# snc98_3x4_Switch-futuba.net
KiCad netlist of a schematic drawn in EAGLE
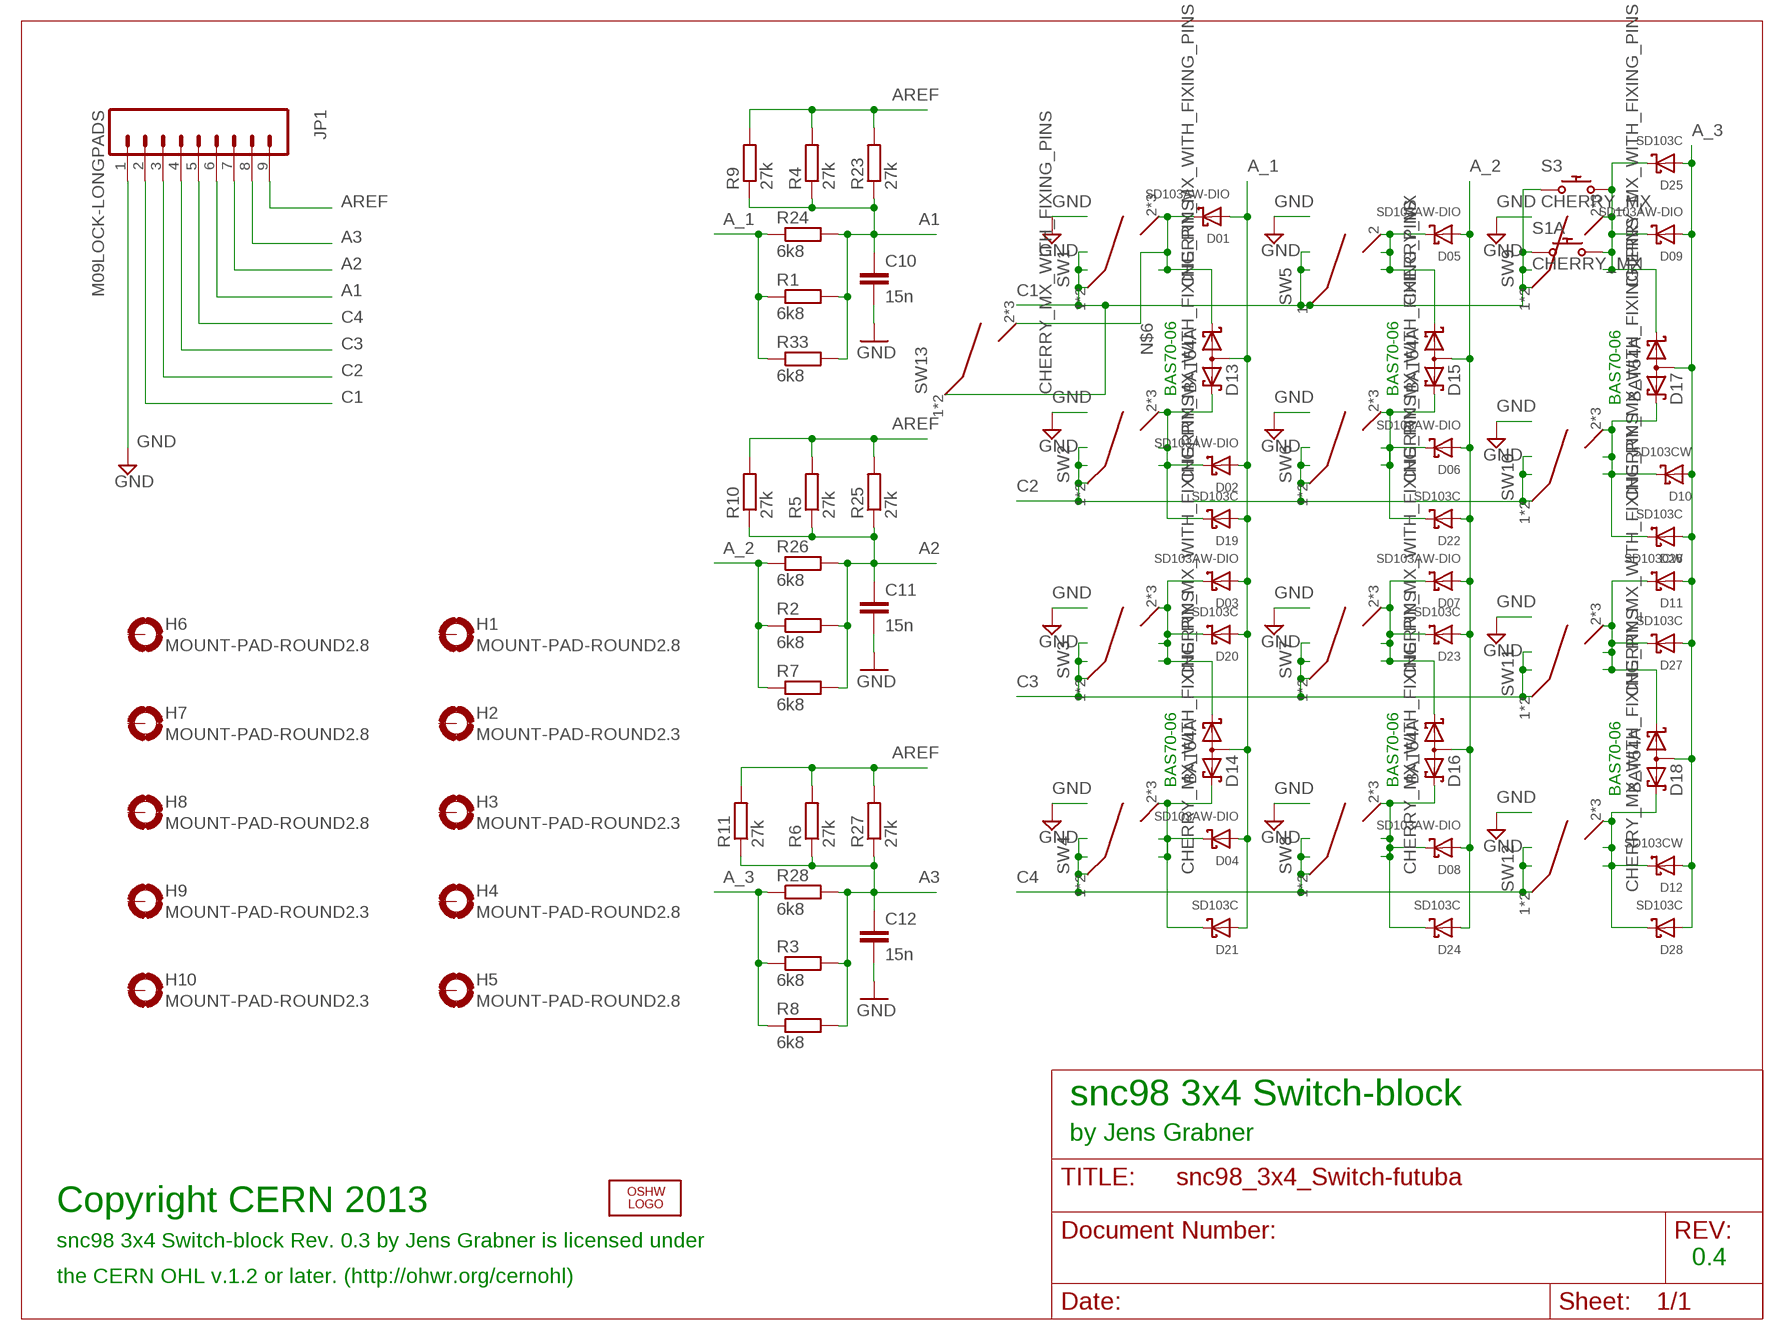
[diagram p0: schematic, sheet 1]

(export (version "E")
  (design (tool "Eeschema 10.0.6"))
  (components
    (comp (ref "C10")
      (value "15n")
      (footprint "eagle-import:C1206K")
      (libsource (lib "eagle-import") (part "C-EUC1206K"))
    )
    (comp (ref "C11")
      (value "15n")
      (footprint "eagle-import:C1206K")
      (libsource (lib "eagle-import") (part "C-EUC1206K"))
    )
    (comp (ref "C12")
      (value "15n")
      (footprint "eagle-import:C1206K")
      (libsource (lib "eagle-import") (part "C-EUC1206K"))
    )
    (comp (ref "D01")
      (value "SD103AW-DIO")
      (footprint "eagle-import:SOD-123F")
      (fields (field (name "MF") "MULTICOMP") (field (name "MPN") "SD103CW-7-F"))
      (libsource (lib "eagle-import") (part "DIODESOD-123F"))
    )
    (comp (ref "D02")
      (value "SD103AW-DIO")
      (footprint "eagle-import:SOD-123F")
      (fields (field (name "MF") "MULTICOMP") (field (name "MPN") "SD103CW-7-F"))
      (libsource (lib "eagle-import") (part "DIODESOD-123F"))
    )
    (comp (ref "D03")
      (value "SD103AW-DIO")
      (footprint "eagle-import:SOD-123F")
      (fields (field (name "MF") "MULTICOMP") (field (name "MPN") "SD103CW-7-F"))
      (libsource (lib "eagle-import") (part "DIODESOD-123F"))
    )
    (comp (ref "D04")
      (value "SD103AW-DIO")
      (footprint "eagle-import:SOD-123F")
      (fields (field (name "MF") "MULTICOMP") (field (name "MPN") "SD103CW-7-F"))
      (libsource (lib "eagle-import") (part "DIODESOD-123F"))
    )
    (comp (ref "D05")
      (value "SD103AW-DIO")
      (footprint "eagle-import:SOD-123F")
      (fields (field (name "MF") "MULTICOMP") (field (name "MPN") "SD103CW-7-F"))
      (libsource (lib "eagle-import") (part "DIODESOD-123F"))
    )
    (comp (ref "D06")
      (value "SD103AW-DIO")
      (footprint "eagle-import:SOD-123F")
      (fields (field (name "MF") "MULTICOMP") (field (name "MPN") "SD103CW-7-F"))
      (libsource (lib "eagle-import") (part "DIODESOD-123F"))
    )
    (comp (ref "D07")
      (value "SD103AW-DIO")
      (footprint "eagle-import:SOD-123F")
      (fields (field (name "MF") "MULTICOMP") (field (name "MPN") "SD103CW-7-F"))
      (libsource (lib "eagle-import") (part "DIODESOD-123F"))
    )
    (comp (ref "D08")
      (value "SD103AW-DIO")
      (footprint "eagle-import:SOD-123F")
      (fields (field (name "MF") "MULTICOMP") (field (name "MPN") "SD103CW-7-F"))
      (libsource (lib "eagle-import") (part "DIODESOD-123F"))
    )
    (comp (ref "D09")
      (value "SD103AW-DIO")
      (footprint "eagle-import:SOD-123F")
      (fields (field (name "MF") "MULTICOMP") (field (name "MPN") "SD103CW-7-F"))
      (libsource (lib "eagle-import") (part "DIODESOD-123F"))
    )
    (comp (ref "D10")
      (value "SD103CW")
      (footprint "eagle-import:SOD-123F")
      (fields (field (name "MF") "MULTICOMP") (field (name "MPN") "SD103CW-7-F"))
      (libsource (lib "eagle-import") (part "DIODESOD-123F"))
    )
    (comp (ref "D11")
      (value "SD103CW")
      (footprint "eagle-import:SOD-123F")
      (fields (field (name "MF") "MULTICOMP") (field (name "MPN") "SD103CW-7-F"))
      (libsource (lib "eagle-import") (part "DIODESOD-123F"))
    )
    (comp (ref "D12")
      (value "SD103CW")
      (footprint "eagle-import:SOD-123F")
      (fields (field (name "MF") "MULTICOMP") (field (name "MPN") "SD103CW-7-F"))
      (libsource (lib "eagle-import") (part "DIODESOD-123F"))
    )
    (comp (ref "D13")
      (value "BAT54A")
      (footprint "eagle-import:SOT23")
      (libsource (lib "eagle-import") (part "BAT54A"))
    )
    (comp (ref "D14")
      (value "BAT54A")
      (footprint "eagle-import:SOT23")
      (libsource (lib "eagle-import") (part "BAT54A"))
    )
    (comp (ref "D15")
      (value "BAT54A")
      (footprint "eagle-import:SOT23")
      (libsource (lib "eagle-import") (part "BAT54A"))
    )
    (comp (ref "D16")
      (value "BAT54A")
      (footprint "eagle-import:SOT23")
      (libsource (lib "eagle-import") (part "BAT54A"))
    )
    (comp (ref "D17")
      (value "BAT54A")
      (footprint "eagle-import:SOT23")
      (libsource (lib "eagle-import") (part "BAT54A"))
    )
    (comp (ref "D18")
      (value "BAT54A")
      (footprint "eagle-import:SOT23")
      (libsource (lib "eagle-import") (part "BAT54A"))
    )
    (comp (ref "D19")
      (value "SD103C")
      (footprint "eagle-import:280MIL-TH")
      (fields (field (name "MF") "MULTICOMP") (field (name "MPN") "SD103CW-7-F"))
      (libsource (lib "eagle-import") (part "DIODE280MIL-TH"))
    )
    (comp (ref "D20")
      (value "SD103C")
      (footprint "eagle-import:280MIL-TH")
      (fields (field (name "MF") "MULTICOMP") (field (name "MPN") "SD103CW-7-F"))
      (libsource (lib "eagle-import") (part "DIODE280MIL-TH"))
    )
    (comp (ref "D21")
      (value "SD103C")
      (footprint "eagle-import:280MIL-TH")
      (fields (field (name "MF") "MULTICOMP") (field (name "MPN") "SD103CW-7-F"))
      (libsource (lib "eagle-import") (part "DIODE280MIL-TH"))
    )
    (comp (ref "D22")
      (value "SD103C")
      (footprint "eagle-import:280MIL-TH")
      (fields (field (name "MF") "MULTICOMP") (field (name "MPN") "SD103CW-7-F"))
      (libsource (lib "eagle-import") (part "DIODE280MIL-TH"))
    )
    (comp (ref "D23")
      (value "SD103C")
      (footprint "eagle-import:280MIL-TH")
      (fields (field (name "MF") "MULTICOMP") (field (name "MPN") "SD103CW-7-F"))
      (libsource (lib "eagle-import") (part "DIODE280MIL-TH"))
    )
    (comp (ref "D24")
      (value "SD103C")
      (footprint "eagle-import:280MIL-TH")
      (fields (field (name "MF") "MULTICOMP") (field (name "MPN") "SD103CW-7-F"))
      (libsource (lib "eagle-import") (part "DIODE280MIL-TH"))
    )
    (comp (ref "D25")
      (value "SD103C")
      (footprint "eagle-import:280MIL-TH")
      (fields (field (name "MF") "MULTICOMP") (field (name "MPN") "SD103CW-7-F"))
      (libsource (lib "eagle-import") (part "DIODE280MIL-TH"))
    )
    (comp (ref "D26")
      (value "SD103C")
      (footprint "eagle-import:280MIL-TH")
      (fields (field (name "MF") "MULTICOMP") (field (name "MPN") "SD103CW-7-F"))
      (libsource (lib "eagle-import") (part "DIODE280MIL-TH"))
    )
    (comp (ref "D27")
      (value "SD103C")
      (footprint "eagle-import:280MIL-TH")
      (fields (field (name "MF") "MULTICOMP") (field (name "MPN") "SD103CW-7-F"))
      (libsource (lib "eagle-import") (part "DIODE280MIL-TH"))
    )
    (comp (ref "D28")
      (value "SD103C")
      (footprint "eagle-import:280MIL-TH")
      (fields (field (name "MF") "MULTICOMP") (field (name "MPN") "SD103CW-7-F"))
      (libsource (lib "eagle-import") (part "DIODE280MIL-TH"))
    )
    (comp (ref "H1")
      (value "MOUNT-PAD-ROUND2.8")
      (footprint "eagle-import:2,8-PAD")
      (libsource (lib "eagle-import") (part "MOUNT-PAD-ROUND2.8"))
    )
    (comp (ref "H2")
      (value "MOUNT-PAD-ROUND2.3")
      (footprint "eagle-import:2,3-PAD")
      (libsource (lib "eagle-import") (part "MOUNT-PAD-ROUND2.3"))
    )
    (comp (ref "H3")
      (value "MOUNT-PAD-ROUND2.3")
      (footprint "eagle-import:2,3-PAD")
      (libsource (lib "eagle-import") (part "MOUNT-PAD-ROUND2.3"))
    )
    (comp (ref "H4")
      (value "MOUNT-PAD-ROUND2.8")
      (footprint "eagle-import:2,8-PAD")
      (libsource (lib "eagle-import") (part "MOUNT-PAD-ROUND2.8"))
    )
    (comp (ref "H5")
      (value "MOUNT-PAD-ROUND2.8")
      (footprint "eagle-import:2,8-PAD")
      (libsource (lib "eagle-import") (part "MOUNT-PAD-ROUND2.8"))
    )
    (comp (ref "H6")
      (value "MOUNT-PAD-ROUND2.8")
      (footprint "eagle-import:2,8-PAD")
      (libsource (lib "eagle-import") (part "MOUNT-PAD-ROUND2.8"))
    )
    (comp (ref "H7")
      (value "MOUNT-PAD-ROUND2.8")
      (footprint "eagle-import:2,8-PAD")
      (libsource (lib "eagle-import") (part "MOUNT-PAD-ROUND2.8"))
    )
    (comp (ref "H8")
      (value "MOUNT-PAD-ROUND2.8")
      (footprint "eagle-import:2,8-PAD")
      (libsource (lib "eagle-import") (part "MOUNT-PAD-ROUND2.8"))
    )
    (comp (ref "H9")
      (value "MOUNT-PAD-ROUND2.3")
      (footprint "eagle-import:2,3-PAD")
      (libsource (lib "eagle-import") (part "MOUNT-PAD-ROUND2.3"))
    )
    (comp (ref "H10")
      (value "MOUNT-PAD-ROUND2.3")
      (footprint "eagle-import:2,3-PAD")
      (libsource (lib "eagle-import") (part "MOUNT-PAD-ROUND2.3"))
    )
    (comp (ref "JP1")
      (value "M09LOCK-LONGPADS")
      (footprint "eagle-import:1X09_LOCK_LONGPADS")
      (libsource (lib "eagle-import") (part "M09LOCK-LONGPADS"))
    )
    (comp (ref "LOGO1")
      (value "OSHW_LOGO_8MILX0150-NT")
      (footprint "eagle-import:OSHW_8X150_NOTEXT")
      (libsource (lib "eagle-import") (part "OSHW_LOGO_8MILX0150-NT"))
    )
    (comp (ref "R1")
      (value "6k8")
      (footprint "eagle-import:R1206")
      (libsource (lib "eagle-import") (part "R-EU_R1206"))
    )
    (comp (ref "R2")
      (value "6k8")
      (footprint "eagle-import:R1206")
      (libsource (lib "eagle-import") (part "R-EU_R1206"))
    )
    (comp (ref "R3")
      (value "6k8")
      (footprint "eagle-import:R1206")
      (libsource (lib "eagle-import") (part "R-EU_R1206"))
    )
    (comp (ref "R4")
      (value "27k")
      (footprint "eagle-import:R1206")
      (libsource (lib "eagle-import") (part "R-EU_R1206"))
    )
    (comp (ref "R5")
      (value "27k")
      (footprint "eagle-import:R1206")
      (libsource (lib "eagle-import") (part "R-EU_R1206"))
    )
    (comp (ref "R6")
      (value "27k")
      (footprint "eagle-import:R1206")
      (libsource (lib "eagle-import") (part "R-EU_R1206"))
    )
    (comp (ref "R7")
      (value "6k8")
      (footprint "eagle-import:M0805")
      (libsource (lib "eagle-import") (part "R-EU_M0805"))
    )
    (comp (ref "R8")
      (value "6k8")
      (footprint "eagle-import:M0805")
      (libsource (lib "eagle-import") (part "R-EU_M0805"))
    )
    (comp (ref "R9")
      (value "27k")
      (footprint "eagle-import:M0805")
      (libsource (lib "eagle-import") (part "R-EU_M0805"))
    )
    (comp (ref "R10")
      (value "27k")
      (footprint "eagle-import:M0805")
      (libsource (lib "eagle-import") (part "R-EU_M0805"))
    )
    (comp (ref "R11")
      (value "27k")
      (footprint "eagle-import:M0805")
      (libsource (lib "eagle-import") (part "R-EU_M0805"))
    )
    (comp (ref "R23")
      (value "27k")
      (footprint "eagle-import:0204_5")
      (libsource (lib "eagle-import") (part "R-EU_0204/5"))
    )
    (comp (ref "R24")
      (value "6k8")
      (footprint "eagle-import:0204_5")
      (libsource (lib "eagle-import") (part "R-EU_0204/5"))
    )
    (comp (ref "R25")
      (value "27k")
      (footprint "eagle-import:0204_5")
      (libsource (lib "eagle-import") (part "R-EU_0204/5"))
    )
    (comp (ref "R26")
      (value "6k8")
      (footprint "eagle-import:0204_5")
      (libsource (lib "eagle-import") (part "R-EU_0204/5"))
    )
    (comp (ref "R27")
      (value "27k")
      (footprint "eagle-import:0204_5")
      (libsource (lib "eagle-import") (part "R-EU_0204/5"))
    )
    (comp (ref "R28")
      (value "6k8")
      (footprint "eagle-import:0204_5")
      (libsource (lib "eagle-import") (part "R-EU_0204/5"))
    )
    (comp (ref "R33")
      (value "6k8")
      (footprint "eagle-import:M0805")
      (libsource (lib "eagle-import") (part "R-EU_M0805"))
    )
    (comp (ref "S1A")
      (value "CHERRY_MX")
      (footprint "eagle-import:CHERRY_MX")
      (libsource (lib "eagle-import") (part "cherry_CHERRY_MX"))
    )
    (comp (ref "S3")
      (value "CHERRY_MX")
      (footprint "eagle-import:CHERRY_MX")
      (libsource (lib "eagle-import") (part "cherry_CHERRY_MX"))
    )
    (comp (ref "SW1")
      (value "CHERRY_MX_WITH_FIXING_PINS")
      (footprint "eagle-import:MX1A-XXNW")
      (libsource (lib "eagle-import") (part "CHERRY_MX_WITH_FIXING_PINS"))
    )
    (comp (ref "SW2")
      (value "CHERRY_MX_WITH_FIXING_PINS")
      (footprint "eagle-import:MX1A-XXNW")
      (libsource (lib "eagle-import") (part "CHERRY_MX_WITH_FIXING_PINS"))
    )
    (comp (ref "SW3")
      (value "CHERRY_MX_WITH_FIXING_PINS")
      (footprint "eagle-import:MX1A-XXNW")
      (libsource (lib "eagle-import") (part "CHERRY_MX_WITH_FIXING_PINS"))
    )
    (comp (ref "SW4")
      (value "CHERRY_MX_WITH_FIXING_PINS")
      (footprint "eagle-import:MX1A-XXNW")
      (libsource (lib "eagle-import") (part "CHERRY_MX_WITH_FIXING_PINS"))
    )
    (comp (ref "SW5")
      (value "CHERRY_MX")
      (footprint "eagle-import:MX1A-XXNN")
      (libsource (lib "eagle-import") (part "CHERRY_MX"))
    )
    (comp (ref "SW6")
      (value "CHERRY_MX_WITH_FIXING_PINS")
      (footprint "eagle-import:MX1A-XXNW")
      (libsource (lib "eagle-import") (part "CHERRY_MX_WITH_FIXING_PINS"))
    )
    (comp (ref "SW7")
      (value "CHERRY_MX_WITH_FIXING_PINS")
      (footprint "eagle-import:MX1A-XXNW")
      (libsource (lib "eagle-import") (part "CHERRY_MX_WITH_FIXING_PINS"))
    )
    (comp (ref "SW8")
      (value "CHERRY_MX_WITH_FIXING_PINS")
      (footprint "eagle-import:MX1A-XXNW")
      (libsource (lib "eagle-import") (part "CHERRY_MX_WITH_FIXING_PINS"))
    )
    (comp (ref "SW9")
      (value "CHERRY_MX_WITH_FIXING_PINS")
      (footprint "eagle-import:MX1A-XXNW")
      (libsource (lib "eagle-import") (part "CHERRY_MX_WITH_FIXING_PINS"))
    )
    (comp (ref "SW10")
      (value "CHERRY_MX_WITH_FIXING_PINS")
      (footprint "eagle-import:MX1A-XXNW")
      (libsource (lib "eagle-import") (part "CHERRY_MX_WITH_FIXING_PINS"))
    )
    (comp (ref "SW11")
      (value "CHERRY_MX_WITH_FIXING_PINS")
      (footprint "eagle-import:MX1A-XXNW")
      (libsource (lib "eagle-import") (part "CHERRY_MX_WITH_FIXING_PINS"))
    )
    (comp (ref "SW12")
      (value "CHERRY_MX_WITH_FIXING_PINS")
      (footprint "eagle-import:MX1A-XXNW")
      (libsource (lib "eagle-import") (part "CHERRY_MX_WITH_FIXING_PINS"))
    )
    (comp (ref "SW13")
      (value "CHERRY_MX_WITH_FIXING_PINS")
      (footprint "eagle-import:MX1A-XXNW")
      (libsource (lib "eagle-import") (part "CHERRY_MX_WITH_FIXING_PINS"))
    )
  )
  (nets
    (net (code "1") (name "/A1") (class "Default")
      (node (ref "C10") (pin "1") (pinfunction "1_1") (pintype "passive"))
      (node (ref "JP1") (pin "6") (pinfunction "6_6") (pintype "passive"))
      (node (ref "R1") (pin "2") (pinfunction "2_2") (pintype "passive"))
      (node (ref "R23") (pin "1") (pinfunction "1_1") (pintype "passive"))
      (node (ref "R24") (pin "2") (pinfunction "2_2") (pintype "passive"))
      (node (ref "R33") (pin "2") (pinfunction "2_2") (pintype "passive"))
      (node (ref "R4") (pin "1") (pinfunction "1_1") (pintype "passive"))
      (node (ref "R9") (pin "1") (pinfunction "1_1") (pintype "passive"))
    )
    (net (code "2") (name "/A2") (class "Default")
      (node (ref "C11") (pin "1") (pinfunction "1_1") (pintype "passive"))
      (node (ref "JP1") (pin "7") (pinfunction "7_7") (pintype "passive"))
      (node (ref "R10") (pin "1") (pinfunction "1_1") (pintype "passive"))
      (node (ref "R2") (pin "2") (pinfunction "2_2") (pintype "passive"))
      (node (ref "R25") (pin "1") (pinfunction "1_1") (pintype "passive"))
      (node (ref "R26") (pin "2") (pinfunction "2_2") (pintype "passive"))
      (node (ref "R5") (pin "1") (pinfunction "1_1") (pintype "passive"))
      (node (ref "R7") (pin "2") (pinfunction "2_2") (pintype "passive"))
    )
    (net (code "3") (name "/A3") (class "Default")
      (node (ref "C12") (pin "1") (pinfunction "1_1") (pintype "passive"))
      (node (ref "JP1") (pin "8") (pinfunction "8_8") (pintype "passive"))
      (node (ref "R11") (pin "1") (pinfunction "1_1") (pintype "passive"))
      (node (ref "R27") (pin "1") (pinfunction "1_1") (pintype "passive"))
      (node (ref "R28") (pin "2") (pinfunction "2_2") (pintype "passive"))
      (node (ref "R3") (pin "2") (pinfunction "2_2") (pintype "passive"))
      (node (ref "R6") (pin "1") (pinfunction "1_1") (pintype "passive"))
      (node (ref "R8") (pin "2") (pinfunction "2_2") (pintype "passive"))
    )
    (net (code "4") (name "/AREF") (class "Default")
      (node (ref "JP1") (pin "9") (pinfunction "9_9") (pintype "passive"))
      (node (ref "R10") (pin "2") (pinfunction "2_2") (pintype "passive"))
      (node (ref "R11") (pin "2") (pinfunction "2_2") (pintype "passive"))
      (node (ref "R23") (pin "2") (pinfunction "2_2") (pintype "passive"))
      (node (ref "R25") (pin "2") (pinfunction "2_2") (pintype "passive"))
      (node (ref "R27") (pin "2") (pinfunction "2_2") (pintype "passive"))
      (node (ref "R4") (pin "2") (pinfunction "2_2") (pintype "passive"))
      (node (ref "R5") (pin "2") (pinfunction "2_2") (pintype "passive"))
      (node (ref "R6") (pin "2") (pinfunction "2_2") (pintype "passive"))
      (node (ref "R9") (pin "2") (pinfunction "2_2") (pintype "passive"))
    )
    (net (code "5") (name "/A_1") (class "Default")
      (node (ref "D01") (pin "A") (pinfunction "A_A") (pintype "passive"))
      (node (ref "D02") (pin "A") (pinfunction "A_A") (pintype "passive"))
      (node (ref "D03") (pin "A") (pinfunction "A_A") (pintype "passive"))
      (node (ref "D04") (pin "A") (pinfunction "A_A") (pintype "passive"))
      (node (ref "D13") (pin "3") (pinfunction "AA_3") (pintype "passive"))
      (node (ref "D14") (pin "3") (pinfunction "AA_3") (pintype "passive"))
      (node (ref "D19") (pin "P$1") (pinfunction "A_P$1") (pintype "passive"))
      (node (ref "D20") (pin "P$1") (pinfunction "A_P$1") (pintype "passive"))
      (node (ref "D21") (pin "P$1") (pinfunction "A_P$1") (pintype "passive"))
      (node (ref "R1") (pin "1") (pinfunction "1_1") (pintype "passive"))
      (node (ref "R24") (pin "1") (pinfunction "1_1") (pintype "passive"))
      (node (ref "R33") (pin "1") (pinfunction "1_1") (pintype "passive"))
    )
    (net (code "6") (name "/A_2") (class "Default")
      (node (ref "D05") (pin "A") (pinfunction "A_A") (pintype "passive"))
      (node (ref "D06") (pin "A") (pinfunction "A_A") (pintype "passive"))
      (node (ref "D07") (pin "A") (pinfunction "A_A") (pintype "passive"))
      (node (ref "D08") (pin "A") (pinfunction "A_A") (pintype "passive"))
      (node (ref "D15") (pin "3") (pinfunction "AA_3") (pintype "passive"))
      (node (ref "D16") (pin "3") (pinfunction "AA_3") (pintype "passive"))
      (node (ref "D22") (pin "P$1") (pinfunction "A_P$1") (pintype "passive"))
      (node (ref "D23") (pin "P$1") (pinfunction "A_P$1") (pintype "passive"))
      (node (ref "D24") (pin "P$1") (pinfunction "A_P$1") (pintype "passive"))
      (node (ref "R2") (pin "1") (pinfunction "1_1") (pintype "passive"))
      (node (ref "R26") (pin "1") (pinfunction "1_1") (pintype "passive"))
      (node (ref "R7") (pin "1") (pinfunction "1_1") (pintype "passive"))
    )
    (net (code "7") (name "/A_3") (class "Default")
      (node (ref "D09") (pin "A") (pinfunction "A_A") (pintype "passive"))
      (node (ref "D10") (pin "A") (pinfunction "A_A") (pintype "passive"))
      (node (ref "D11") (pin "A") (pinfunction "A_A") (pintype "passive"))
      (node (ref "D12") (pin "A") (pinfunction "A_A") (pintype "passive"))
      (node (ref "D17") (pin "3") (pinfunction "AA_3") (pintype "passive"))
      (node (ref "D18") (pin "3") (pinfunction "AA_3") (pintype "passive"))
      (node (ref "D25") (pin "P$1") (pinfunction "A_P$1") (pintype "passive"))
      (node (ref "D26") (pin "P$1") (pinfunction "A_P$1") (pintype "passive"))
      (node (ref "D27") (pin "P$1") (pinfunction "A_P$1") (pintype "passive"))
      (node (ref "D28") (pin "P$1") (pinfunction "A_P$1") (pintype "passive"))
      (node (ref "R28") (pin "1") (pinfunction "1_1") (pintype "passive"))
      (node (ref "R3") (pin "1") (pinfunction "1_1") (pintype "passive"))
      (node (ref "R8") (pin "1") (pinfunction "1_1") (pintype "passive"))
    )
    (net (code "8") (name "/C1") (class "Default")
      (node (ref "JP1") (pin "2") (pinfunction "2_2") (pintype "passive"))
      (node (ref "S1A") (pin "S1") (pinfunction "1_S1") (pintype "passive"))
      (node (ref "S3") (pin "S1") (pinfunction "1_S1") (pintype "passive"))
      (node (ref "SW1") (pin "1") (pinfunction "1_1") (pintype "passive"))
      (node (ref "SW1") (pin "3") (pinfunction "1_3") (pintype "passive"))
      (node (ref "SW13") (pin "1") (pinfunction "1_1") (pintype "passive"))
      (node (ref "SW13") (pin "3") (pinfunction "1_3") (pintype "passive"))
      (node (ref "SW5") (pin "1") (pinfunction "1_1") (pintype "passive"))
      (node (ref "SW9") (pin "1") (pinfunction "1_1") (pintype "passive"))
      (node (ref "SW9") (pin "3") (pinfunction "1_3") (pintype "passive"))
    )
    (net (code "9") (name "/C2") (class "Default")
      (node (ref "JP1") (pin "3") (pinfunction "3_3") (pintype "passive"))
      (node (ref "SW10") (pin "1") (pinfunction "1_1") (pintype "passive"))
      (node (ref "SW10") (pin "3") (pinfunction "1_3") (pintype "passive"))
      (node (ref "SW2") (pin "1") (pinfunction "1_1") (pintype "passive"))
      (node (ref "SW2") (pin "3") (pinfunction "1_3") (pintype "passive"))
      (node (ref "SW6") (pin "1") (pinfunction "1_1") (pintype "passive"))
      (node (ref "SW6") (pin "3") (pinfunction "1_3") (pintype "passive"))
    )
    (net (code "10") (name "/C3") (class "Default")
      (node (ref "JP1") (pin "4") (pinfunction "4_4") (pintype "passive"))
      (node (ref "SW11") (pin "1") (pinfunction "1_1") (pintype "passive"))
      (node (ref "SW11") (pin "3") (pinfunction "1_3") (pintype "passive"))
      (node (ref "SW3") (pin "1") (pinfunction "1_1") (pintype "passive"))
      (node (ref "SW3") (pin "3") (pinfunction "1_3") (pintype "passive"))
      (node (ref "SW7") (pin "1") (pinfunction "1_1") (pintype "passive"))
      (node (ref "SW7") (pin "3") (pinfunction "1_3") (pintype "passive"))
    )
    (net (code "11") (name "/C4") (class "Default")
      (node (ref "JP1") (pin "5") (pinfunction "5_5") (pintype "passive"))
      (node (ref "SW12") (pin "1") (pinfunction "1_1") (pintype "passive"))
      (node (ref "SW12") (pin "3") (pinfunction "1_3") (pintype "passive"))
      (node (ref "SW4") (pin "1") (pinfunction "1_1") (pintype "passive"))
      (node (ref "SW4") (pin "3") (pinfunction "1_3") (pintype "passive"))
      (node (ref "SW8") (pin "1") (pinfunction "1_1") (pintype "passive"))
      (node (ref "SW8") (pin "3") (pinfunction "1_3") (pintype "passive"))
    )
    (net (code "12") (name "/N$6") (class "Default")
      (node (ref "D01") (pin "C") (pinfunction "C_C") (pintype "passive"))
      (node (ref "D13") (pin "1") (pinfunction "K1_1") (pintype "passive"))
      (node (ref "SW1") (pin "2") (pinfunction "2_2") (pintype "passive"))
      (node (ref "SW1") (pin "4") (pinfunction "2_4") (pintype "passive"))
      (node (ref "SW1") (pin "5") (pinfunction "2_5") (pintype "passive"))
      (node (ref "SW13") (pin "2") (pinfunction "2_2") (pintype "passive"))
      (node (ref "SW13") (pin "4") (pinfunction "2_4") (pintype "passive"))
      (node (ref "SW13") (pin "5") (pinfunction "2_5") (pintype "passive"))
    )
    (net (code "13") (name "GND") (class "Default")
      (node (ref "C10") (pin "2") (pinfunction "2_2") (pintype "passive"))
      (node (ref "C11") (pin "2") (pinfunction "2_2") (pintype "passive"))
      (node (ref "C12") (pin "2") (pinfunction "2_2") (pintype "passive"))
      (node (ref "JP1") (pin "1") (pinfunction "1_1") (pintype "passive"))
    )
    (net (code "14") (name "Net-(D13-K2)") (class "Default")
      (node (ref "D02") (pin "C") (pinfunction "C_C") (pintype "passive"))
      (node (ref "D13") (pin "2") (pinfunction "K2_2") (pintype "passive"))
      (node (ref "D19") (pin "P$2") (pinfunction "C_P$2") (pintype "passive"))
      (node (ref "SW2") (pin "2") (pinfunction "2_2") (pintype "passive"))
      (node (ref "SW2") (pin "4") (pinfunction "2_4") (pintype "passive"))
      (node (ref "SW2") (pin "5") (pinfunction "2_5") (pintype "passive"))
    )
    (net (code "15") (name "Net-(D14-K1)") (class "Default")
      (node (ref "D03") (pin "C") (pinfunction "C_C") (pintype "passive"))
      (node (ref "D14") (pin "1") (pinfunction "K1_1") (pintype "passive"))
      (node (ref "D20") (pin "P$2") (pinfunction "C_P$2") (pintype "passive"))
      (node (ref "SW3") (pin "2") (pinfunction "2_2") (pintype "passive"))
      (node (ref "SW3") (pin "4") (pinfunction "2_4") (pintype "passive"))
      (node (ref "SW3") (pin "5") (pinfunction "2_5") (pintype "passive"))
    )
    (net (code "16") (name "Net-(D14-K2)") (class "Default")
      (node (ref "D04") (pin "C") (pinfunction "C_C") (pintype "passive"))
      (node (ref "D14") (pin "2") (pinfunction "K2_2") (pintype "passive"))
      (node (ref "D21") (pin "P$2") (pinfunction "C_P$2") (pintype "passive"))
      (node (ref "SW4") (pin "2") (pinfunction "2_2") (pintype "passive"))
      (node (ref "SW4") (pin "4") (pinfunction "2_4") (pintype "passive"))
      (node (ref "SW4") (pin "5") (pinfunction "2_5") (pintype "passive"))
    )
    (net (code "17") (name "Net-(D15-K1)") (class "Default")
      (node (ref "D05") (pin "C") (pinfunction "C_C") (pintype "passive"))
      (node (ref "D15") (pin "1") (pinfunction "K1_1") (pintype "passive"))
      (node (ref "SW5") (pin "2") (pinfunction "2_2") (pintype "passive"))
    )
    (net (code "18") (name "Net-(D15-K2)") (class "Default")
      (node (ref "D06") (pin "C") (pinfunction "C_C") (pintype "passive"))
      (node (ref "D15") (pin "2") (pinfunction "K2_2") (pintype "passive"))
      (node (ref "D22") (pin "P$2") (pinfunction "C_P$2") (pintype "passive"))
      (node (ref "SW6") (pin "2") (pinfunction "2_2") (pintype "passive"))
      (node (ref "SW6") (pin "4") (pinfunction "2_4") (pintype "passive"))
      (node (ref "SW6") (pin "5") (pinfunction "2_5") (pintype "passive"))
    )
    (net (code "19") (name "Net-(D16-K1)") (class "Default")
      (node (ref "D07") (pin "C") (pinfunction "C_C") (pintype "passive"))
      (node (ref "D16") (pin "1") (pinfunction "K1_1") (pintype "passive"))
      (node (ref "D23") (pin "P$2") (pinfunction "C_P$2") (pintype "passive"))
      (node (ref "SW7") (pin "2") (pinfunction "2_2") (pintype "passive"))
      (node (ref "SW7") (pin "4") (pinfunction "2_4") (pintype "passive"))
      (node (ref "SW7") (pin "5") (pinfunction "2_5") (pintype "passive"))
    )
    (net (code "20") (name "Net-(D16-K2)") (class "Default")
      (node (ref "D08") (pin "C") (pinfunction "C_C") (pintype "passive"))
      (node (ref "D16") (pin "2") (pinfunction "K2_2") (pintype "passive"))
      (node (ref "D24") (pin "P$2") (pinfunction "C_P$2") (pintype "passive"))
      (node (ref "SW8") (pin "2") (pinfunction "2_2") (pintype "passive"))
      (node (ref "SW8") (pin "4") (pinfunction "2_4") (pintype "passive"))
      (node (ref "SW8") (pin "5") (pinfunction "2_5") (pintype "passive"))
    )
    (net (code "21") (name "Net-(D17-K1)") (class "Default")
      (node (ref "D09") (pin "C") (pinfunction "C_C") (pintype "passive"))
      (node (ref "D17") (pin "1") (pinfunction "K1_1") (pintype "passive"))
      (node (ref "D25") (pin "P$2") (pinfunction "C_P$2") (pintype "passive"))
      (node (ref "S1A") (pin "S2") (pinfunction "2_S2") (pintype "passive"))
      (node (ref "S3") (pin "S2") (pinfunction "2_S2") (pintype "passive"))
      (node (ref "SW9") (pin "2") (pinfunction "2_2") (pintype "passive"))
      (node (ref "SW9") (pin "4") (pinfunction "2_4") (pintype "passive"))
      (node (ref "SW9") (pin "5") (pinfunction "2_5") (pintype "passive"))
    )
    (net (code "22") (name "Net-(D17-K2)") (class "Default")
      (node (ref "D10") (pin "C") (pinfunction "C_C") (pintype "passive"))
      (node (ref "D17") (pin "2") (pinfunction "K2_2") (pintype "passive"))
      (node (ref "D26") (pin "P$2") (pinfunction "C_P$2") (pintype "passive"))
      (node (ref "SW10") (pin "2") (pinfunction "2_2") (pintype "passive"))
      (node (ref "SW10") (pin "4") (pinfunction "2_4") (pintype "passive"))
      (node (ref "SW10") (pin "5") (pinfunction "2_5") (pintype "passive"))
    )
    (net (code "23") (name "Net-(D18-K1)") (class "Default")
      (node (ref "D11") (pin "C") (pinfunction "C_C") (pintype "passive"))
      (node (ref "D18") (pin "1") (pinfunction "K1_1") (pintype "passive"))
      (node (ref "D27") (pin "P$2") (pinfunction "C_P$2") (pintype "passive"))
      (node (ref "SW11") (pin "2") (pinfunction "2_2") (pintype "passive"))
      (node (ref "SW11") (pin "4") (pinfunction "2_4") (pintype "passive"))
      (node (ref "SW11") (pin "5") (pinfunction "2_5") (pintype "passive"))
    )
    (net (code "24") (name "Net-(D18-K2)") (class "Default")
      (node (ref "D12") (pin "C") (pinfunction "C_C") (pintype "passive"))
      (node (ref "D18") (pin "2") (pinfunction "K2_2") (pintype "passive"))
      (node (ref "D28") (pin "P$2") (pinfunction "C_P$2") (pintype "passive"))
      (node (ref "SW12") (pin "2") (pinfunction "2_2") (pintype "passive"))
      (node (ref "SW12") (pin "4") (pinfunction "2_4") (pintype "passive"))
      (node (ref "SW12") (pin "5") (pinfunction "2_5") (pintype "passive"))
    )
    (net (code "25") (name "unconnected-(H1-MOUNT-PadB2,8)") (class "Default")
      (node (ref "H1") (pin "B2,8") (pinfunction "MOUNT_B2,8") (pintype "passive"))
    )
    (net (code "26") (name "unconnected-(H2-MOUNT-PadB2,8)") (class "Default")
      (node (ref "H2") (pin "B2,8") (pinfunction "MOUNT_B2,8") (pintype "passive"))
    )
    (net (code "27") (name "unconnected-(H3-MOUNT-PadB2,8)") (class "Default")
      (node (ref "H3") (pin "B2,8") (pinfunction "MOUNT_B2,8") (pintype "passive"))
    )
    (net (code "28") (name "unconnected-(H4-MOUNT-PadB2,8)") (class "Default")
      (node (ref "H4") (pin "B2,8") (pinfunction "MOUNT_B2,8") (pintype "passive"))
    )
    (net (code "29") (name "unconnected-(H5-MOUNT-PadB2,8)") (class "Default")
      (node (ref "H5") (pin "B2,8") (pinfunction "MOUNT_B2,8") (pintype "passive"))
    )
    (net (code "30") (name "unconnected-(H6-MOUNT-PadB2,8)") (class "Default")
      (node (ref "H6") (pin "B2,8") (pinfunction "MOUNT_B2,8") (pintype "passive"))
    )
    (net (code "31") (name "unconnected-(H7-MOUNT-PadB2,8)") (class "Default")
      (node (ref "H7") (pin "B2,8") (pinfunction "MOUNT_B2,8") (pintype "passive"))
    )
    (net (code "32") (name "unconnected-(H8-MOUNT-PadB2,8)") (class "Default")
      (node (ref "H8") (pin "B2,8") (pinfunction "MOUNT_B2,8") (pintype "passive"))
    )
    (net (code "33") (name "unconnected-(H9-MOUNT-PadB2,8)") (class "Default")
      (node (ref "H9") (pin "B2,8") (pinfunction "MOUNT_B2,8") (pintype "passive"))
    )
    (net (code "34") (name "unconnected-(H10-MOUNT-PadB2,8)") (class "Default")
      (node (ref "H10") (pin "B2,8") (pinfunction "MOUNT_B2,8") (pintype "passive"))
    )
  )
)
